# SCH_birdo_2021-11-24.net
KiCad netlist of a schematic drawn in EasyEDA
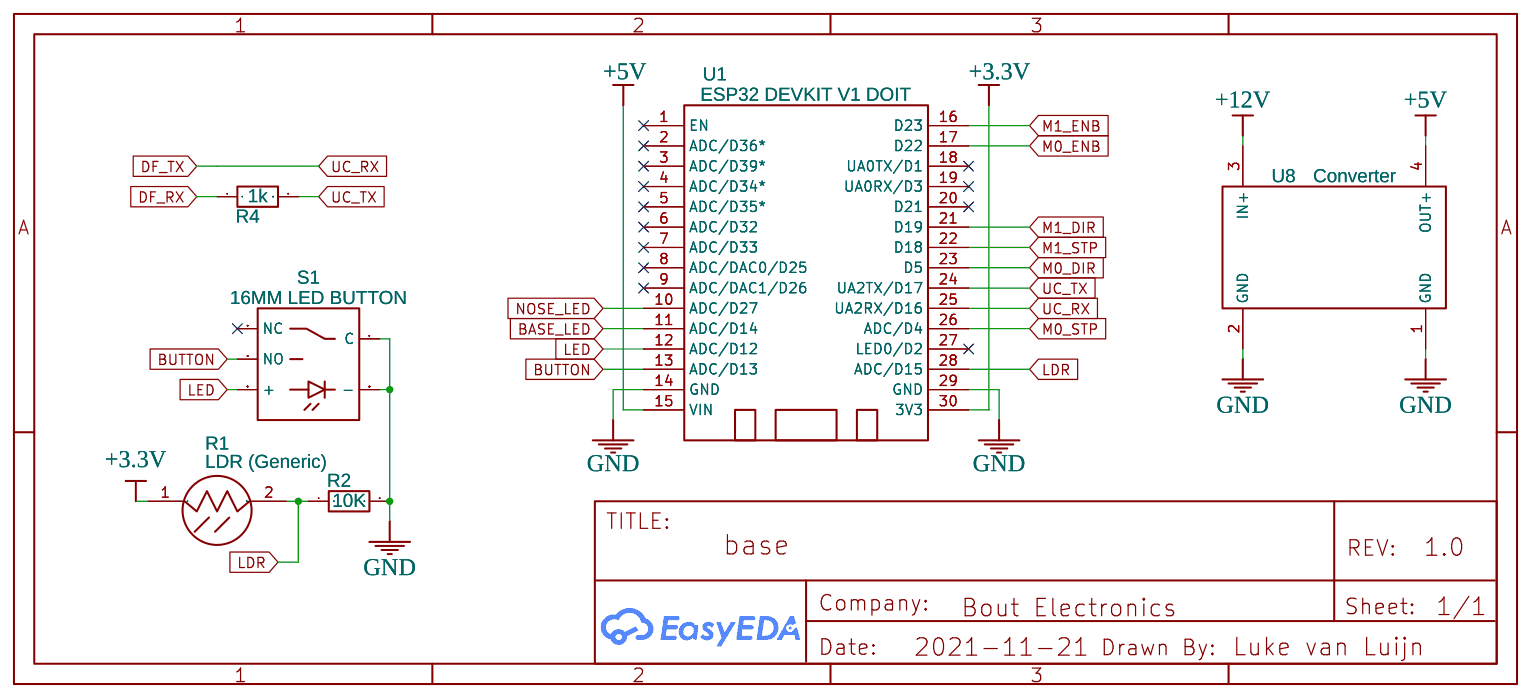
[diagram p0: base]
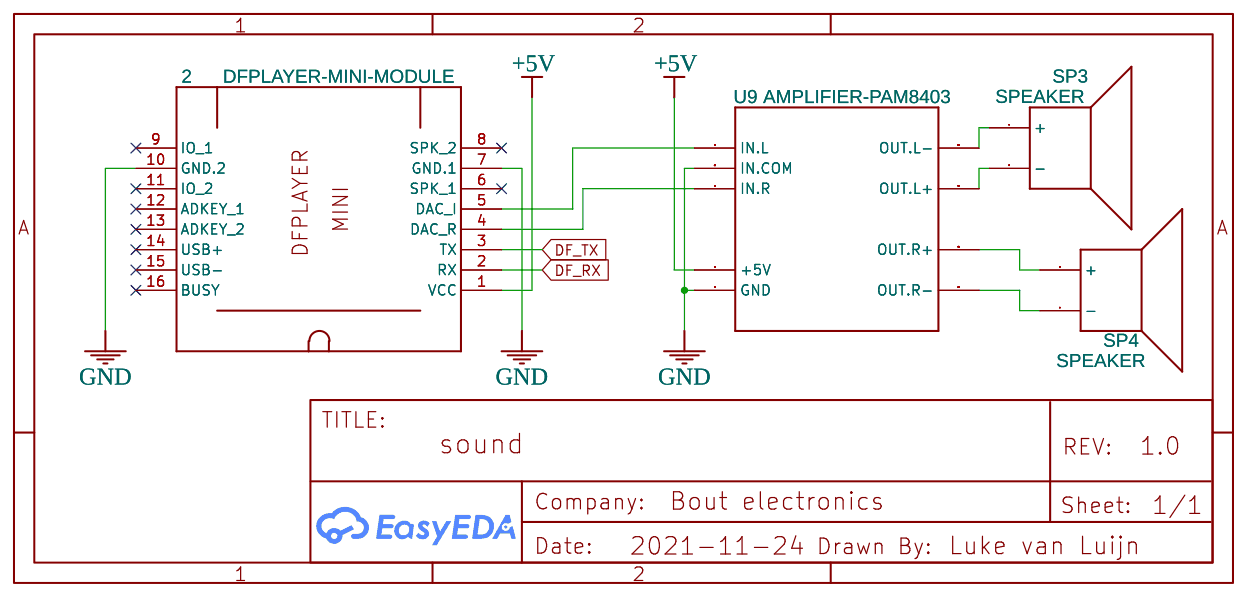
[diagram p1: sound]
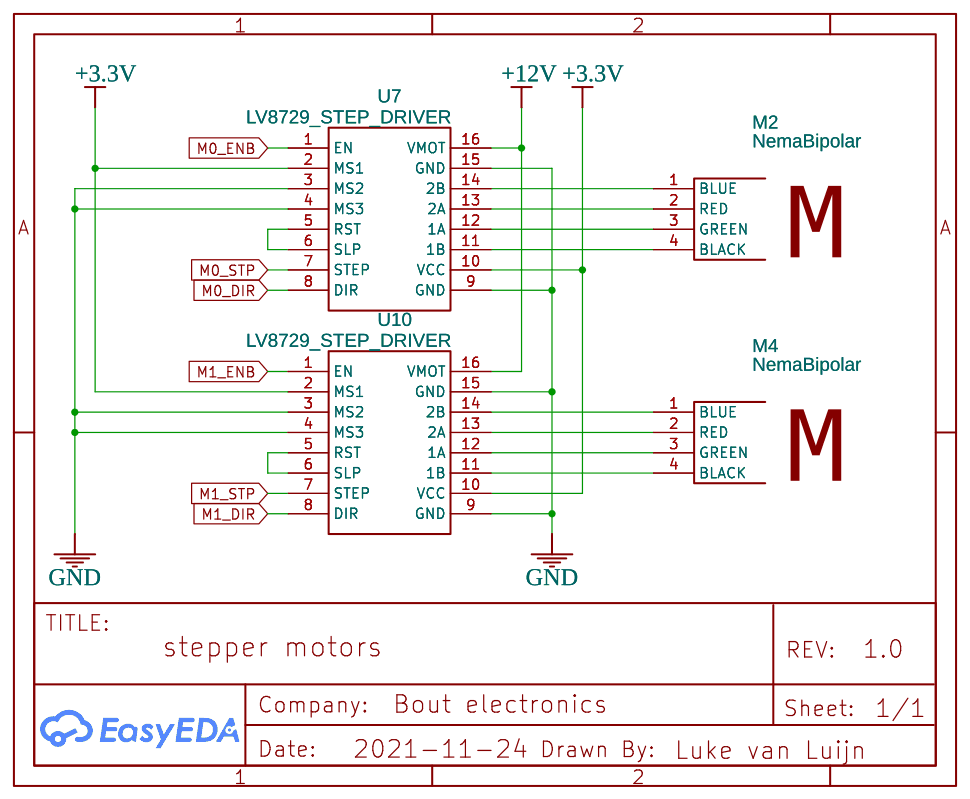
[diagram p2: motors]
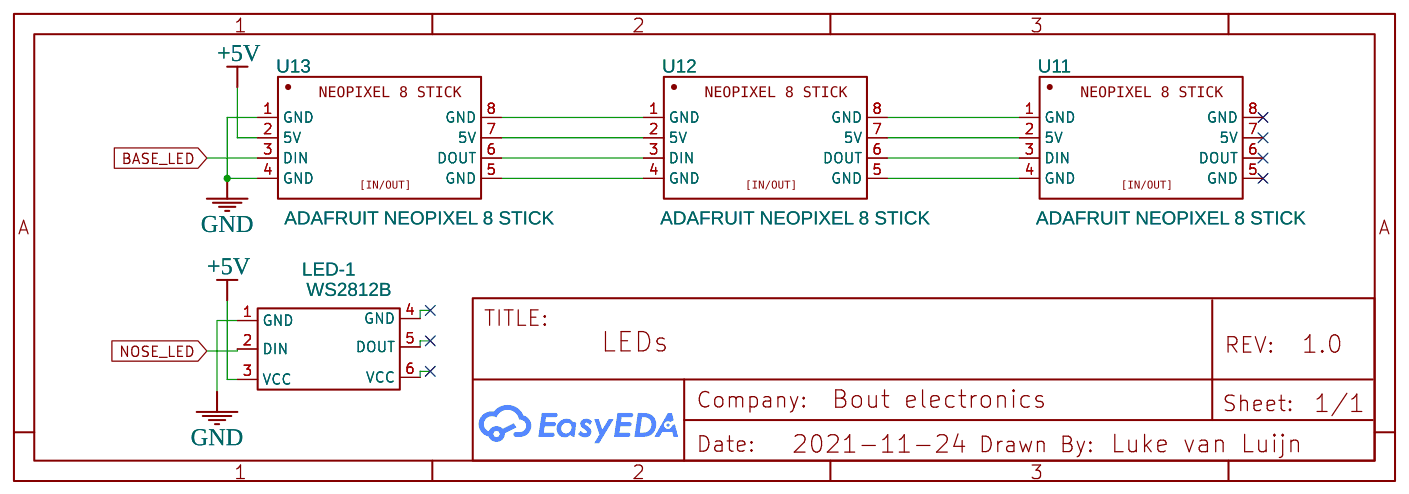
[diagram p3: LEDs]

(export (version "E")
  (design (tool "Eeschema 10.0.6"))
  (components
    (comp (ref "R1") (value "LDR (Generic)") (libsource (lib "") (part "LDR (Generic)")))
    (comp (ref "R2") (value "10K") (libsource (lib "") (part "R_AXIAL-0.3_EU")))
    (comp (ref "R4") (value "1k") (libsource (lib "") (part "R_AXIAL-0.3_EU")))
    (comp (ref "S1")
      (value "16MM LED BUTTON")
      (fields
        (field (name "BOM_Manufacturer Part") "LED BTN")
        (field (name "BOM_Supplier Part") "16mm Momentary Push Button 12V")
      )
      (libsource (lib "") (part "16MM LED 12V MOMENTARY PUSH BUTTON"))
    )
    (comp (ref "U1") (value "ESP32 DEVKIT V1 DOIT") (libsource (lib "") (part "ESP32 DEVKIT V1 DOIT")))
    (comp (ref "U8") (value "Converter") (libsource (lib "") (part "StepDownConverter")))
    (comp (ref "2") (value "DFPLAYER-MINI-MODULE") (libsource (lib "") (part "DFPLAYER-MINI-MODULE")))
    (comp (ref "SP3") (value "SPEAKER") (libsource (lib "") (part "SPEAKER")))
    (comp (ref "SP4") (value "SPEAKER") (libsource (lib "") (part "SPEAKER")))
    (comp (ref "U9") (value "AMPLIFIER-PAM8403") (libsource (lib "") (part "AMPLIFIER-PAM8403")))
    (comp (ref "M2") (value "NemaBipolar") (libsource (lib "") (part "NemaBipolar")))
    (comp (ref "M4") (value "NemaBipolar") (libsource (lib "") (part "NemaBipolar")))
    (comp (ref "U7")
      (value "LV8729_STEP_DRIVER")
      (fields (field (name "BOM_Manufacturer Part") "A4988 MODULE"))
      (libsource (lib "") (part "LV8729_STEP_DRIVER"))
    )
    (comp (ref "U10")
      (value "LV8729_STEP_DRIVER")
      (fields (field (name "BOM_Manufacturer Part") "A4988 MODULE"))
      (libsource (lib "") (part "LV8729_STEP_DRIVER"))
    )
    (comp (ref "LED-1") (value "WS2812B") (libsource (lib "") (part "WS2812B")))
    (comp (ref "U11")
      (value "ADAFRUIT NEOPIXEL 8 STICK")
      (fields (field (name "BOM_Manufacturer Part") "1426") (field (name "BOM_Supplier Part") "1528-1354-ND"))
      (libsource (lib "") (part "ADAFRUIT NEOPIXEL 8 STICK [IN/OUT]"))
    )
    (comp (ref "U12")
      (value "ADAFRUIT NEOPIXEL 8 STICK")
      (fields (field (name "BOM_Manufacturer Part") "1426") (field (name "BOM_Supplier Part") "1528-1354-ND"))
      (libsource (lib "") (part "ADAFRUIT NEOPIXEL 8 STICK [IN/OUT]"))
    )
    (comp (ref "U13")
      (value "ADAFRUIT NEOPIXEL 8 STICK")
      (fields (field (name "BOM_Manufacturer Part") "1426") (field (name "BOM_Supplier Part") "1528-1354-ND"))
      (libsource (lib "") (part "ADAFRUIT NEOPIXEL 8 STICK [IN/OUT]"))
    )
  )
  (nets
    (net (code "1") (name "+3.3V") (class "Default")
      (node (ref "R1") (pin "1") (pinfunction "1_1") (pintype "unspecified"))
      (node (ref "U1") (pin "30") (pinfunction "3V3_30") (pintype "bidirectional"))
      (node (ref "U10") (pin "10") (pinfunction "VCC_10") (pintype "unspecified"))
      (node (ref "U10") (pin "2") (pinfunction "MS1_2") (pintype "unspecified"))
      (node (ref "U7") (pin "10") (pinfunction "VCC_10") (pintype "unspecified"))
      (node (ref "U7") (pin "2") (pinfunction "MS1_2") (pintype "unspecified"))
    )
    (net (code "2") (name "+5V") (class "Default")
      (node (ref "2") (pin "1") (pinfunction "VCC_1") (pintype "bidirectional"))
      (node (ref "LED-1") (pin "3") (pinfunction "VCC_3") (pintype "unspecified"))
      (node (ref "U1") (pin "15") (pinfunction "VIN_15") (pintype "input"))
      (node (ref "U13") (pin "2") (pinfunction "5V_2") (pintype "unspecified"))
      (node (ref "U8") (pin "4") (pinfunction "OUT+_4") (pintype "unspecified"))
      (node (ref "U9") (pin "+5V") (pinfunction "+5V_+5V") (pintype "passive"))
    )
    (net (code "3") (name "+12V") (class "Default")
      (node (ref "U10") (pin "16") (pinfunction "VMOT_16") (pintype "unspecified"))
      (node (ref "U7") (pin "16") (pinfunction "VMOT_16") (pintype "unspecified"))
      (node (ref "U8") (pin "3") (pinfunction "IN+_3") (pintype "unspecified"))
    )
    (net (code "4") (name "BASE_LED") (class "Default")
      (node (ref "U1") (pin "11") (pinfunction "ADC/D14_11") (pintype "bidirectional"))
      (node (ref "U13") (pin "3") (pinfunction "DIN_3") (pintype "unspecified"))
    )
    (net (code "5") (name "BUTTON") (class "Default")
      (node (ref "S1") (pin "NO") (pinfunction "NO_NO") (pintype "unspecified"))
      (node (ref "U1") (pin "13") (pinfunction "ADC/D13_13") (pintype "bidirectional"))
    )
    (net (code "6") (name "DF_RX") (class "Default")
      (node (ref "2") (pin "2") (pinfunction "RX_2") (pintype "bidirectional"))
      (node (ref "R4") (pin "1") (pinfunction "1_1") (pintype "unspecified"))
    )
    (net (code "7") (name "DF_TX") (class "Default")
      (node (ref "2") (pin "3") (pinfunction "TX_3") (pintype "bidirectional"))
      (node (ref "U1") (pin "25") (pinfunction "UA2RX/D16_25") (pintype "bidirectional"))
    )
    (net (code "8") (name "GND") (class "Default")
      (node (ref "2") (pin "10") (pinfunction "GND.2_10") (pintype "bidirectional"))
      (node (ref "2") (pin "7") (pinfunction "GND.1_7") (pintype "bidirectional"))
      (node (ref "LED-1") (pin "1") (pinfunction "GND_1") (pintype "unspecified"))
      (node (ref "R2") (pin "2") (pinfunction "2_2") (pintype "unspecified"))
      (node (ref "S1") (pin "C") (pinfunction "C_C") (pintype "unspecified"))
      (node (ref "S1") (pin "GND") (pinfunction "-_GND") (pintype "unspecified"))
      (node (ref "U1") (pin "14") (pinfunction "GND_14") (pintype "bidirectional"))
      (node (ref "U1") (pin "29") (pinfunction "GND_29") (pintype "bidirectional"))
      (node (ref "U10") (pin "15") (pinfunction "GND_15") (pintype "unspecified"))
      (node (ref "U10") (pin "3") (pinfunction "MS2_3") (pintype "unspecified"))
      (node (ref "U10") (pin "4") (pinfunction "MS3_4") (pintype "unspecified"))
      (node (ref "U10") (pin "9") (pinfunction "GND_9") (pintype "unspecified"))
      (node (ref "U13") (pin "1") (pinfunction "GND_1") (pintype "unspecified"))
      (node (ref "U13") (pin "4") (pinfunction "GND_4") (pintype "unspecified"))
      (node (ref "U7") (pin "15") (pinfunction "GND_15") (pintype "unspecified"))
      (node (ref "U7") (pin "3") (pinfunction "MS2_3") (pintype "unspecified"))
      (node (ref "U7") (pin "4") (pinfunction "MS3_4") (pintype "unspecified"))
      (node (ref "U7") (pin "9") (pinfunction "GND_9") (pintype "unspecified"))
      (node (ref "U8") (pin "1") (pinfunction "GND_1") (pintype "unspecified"))
      (node (ref "U8") (pin "2") (pinfunction "GND_2") (pintype "unspecified"))
      (node (ref "U9") (pin "GND") (pinfunction "GND_GND") (pintype "passive"))
      (node (ref "U9") (pin "IN.COM") (pinfunction "IN.COM_IN.COM") (pintype "input"))
    )
    (net (code "9") (name "LDR") (class "Default")
      (node (ref "R1") (pin "2") (pinfunction "2_2") (pintype "unspecified"))
      (node (ref "R2") (pin "1") (pinfunction "1_1") (pintype "unspecified"))
      (node (ref "U1") (pin "28") (pinfunction "ADC/D15_28") (pintype "bidirectional"))
    )
    (net (code "10") (name "LED") (class "Default")
      (node (ref "S1") (pin "VCC") (pinfunction "+_VCC") (pintype "unspecified"))
      (node (ref "U1") (pin "12") (pinfunction "ADC/D12_12") (pintype "bidirectional"))
    )
    (net (code "11") (name "M0_DIR") (class "Default")
      (node (ref "U1") (pin "23") (pinfunction "D5_23") (pintype "bidirectional"))
      (node (ref "U7") (pin "8") (pinfunction "DIR_8") (pintype "unspecified"))
    )
    (net (code "12") (name "M0_ENB") (class "Default")
      (node (ref "U1") (pin "17") (pinfunction "D22_17") (pintype "bidirectional"))
      (node (ref "U7") (pin "1") (pinfunction "EN_1") (pintype "unspecified"))
    )
    (net (code "13") (name "M0_STP") (class "Default")
      (node (ref "U1") (pin "26") (pinfunction "ADC/D4_26") (pintype "bidirectional"))
      (node (ref "U7") (pin "7") (pinfunction "STEP_7") (pintype "unspecified"))
    )
    (net (code "14") (name "M1_DIR") (class "Default")
      (node (ref "U1") (pin "21") (pinfunction "D19_21") (pintype "bidirectional"))
      (node (ref "U10") (pin "8") (pinfunction "DIR_8") (pintype "unspecified"))
    )
    (net (code "15") (name "M1_ENB") (class "Default")
      (node (ref "U1") (pin "16") (pinfunction "D23_16") (pintype "bidirectional"))
      (node (ref "U10") (pin "1") (pinfunction "EN_1") (pintype "unspecified"))
    )
    (net (code "16") (name "M1_STP") (class "Default")
      (node (ref "U1") (pin "22") (pinfunction "D18_22") (pintype "bidirectional"))
      (node (ref "U10") (pin "7") (pinfunction "STEP_7") (pintype "unspecified"))
    )
    (net (code "17") (name "NOSE_LED") (class "Default")
      (node (ref "LED-1") (pin "2") (pinfunction "DIN_2") (pintype "unspecified"))
      (node (ref "U1") (pin "10") (pinfunction "ADC/D27_10") (pintype "bidirectional"))
    )
    (net (code "18") (name "Net-(2-DAC_I)") (class "Default")
      (node (ref "2") (pin "5") (pinfunction "DAC_I_5") (pintype "bidirectional"))
      (node (ref "U9") (pin "IN.L") (pinfunction "IN.L_IN.L") (pintype "input"))
    )
    (net (code "19") (name "Net-(2-DAC_R)") (class "Default")
      (node (ref "2") (pin "4") (pinfunction "DAC_R_4") (pintype "bidirectional"))
      (node (ref "U9") (pin "IN.R") (pinfunction "IN.R_IN.R") (pintype "unspecified"))
    )
    (net (code "20") (name "Net-(M2-BLACK)") (class "Default")
      (node (ref "M2") (pin "4") (pinfunction "BLACK_4") (pintype "input"))
      (node (ref "U7") (pin "11") (pinfunction "1B_11") (pintype "unspecified"))
    )
    (net (code "21") (name "Net-(M2-BLUE)") (class "Default")
      (node (ref "M2") (pin "1") (pinfunction "BLUE_1") (pintype "input"))
      (node (ref "U7") (pin "14") (pinfunction "2B_14") (pintype "unspecified"))
    )
    (net (code "22") (name "Net-(M2-GREEN)") (class "Default")
      (node (ref "M2") (pin "3") (pinfunction "GREEN_3") (pintype "input"))
      (node (ref "U7") (pin "12") (pinfunction "1A_12") (pintype "unspecified"))
    )
    (net (code "23") (name "Net-(M2-RED)") (class "Default")
      (node (ref "M2") (pin "2") (pinfunction "RED_2") (pintype "input"))
      (node (ref "U7") (pin "13") (pinfunction "2A_13") (pintype "unspecified"))
    )
    (net (code "24") (name "Net-(M4-BLACK)") (class "Default")
      (node (ref "M4") (pin "4") (pinfunction "BLACK_4") (pintype "input"))
      (node (ref "U10") (pin "11") (pinfunction "1B_11") (pintype "unspecified"))
    )
    (net (code "25") (name "Net-(M4-BLUE)") (class "Default")
      (node (ref "M4") (pin "1") (pinfunction "BLUE_1") (pintype "input"))
      (node (ref "U10") (pin "14") (pinfunction "2B_14") (pintype "unspecified"))
    )
    (net (code "26") (name "Net-(M4-GREEN)") (class "Default")
      (node (ref "M4") (pin "3") (pinfunction "GREEN_3") (pintype "input"))
      (node (ref "U10") (pin "12") (pinfunction "1A_12") (pintype "unspecified"))
    )
    (net (code "27") (name "Net-(M4-RED)") (class "Default")
      (node (ref "M4") (pin "2") (pinfunction "RED_2") (pintype "input"))
      (node (ref "U10") (pin "13") (pinfunction "2A_13") (pintype "unspecified"))
    )
    (net (code "28") (name "Net-(SP3-+)") (class "Default")
      (node (ref "SP3") (pin "1") (pinfunction "+_1") (pintype "bidirectional"))
      (node (ref "U9") (pin "OUT.L-") (pinfunction "OUT.L-_OUT.L-") (pintype "output"))
    )
    (net (code "29") (name "Net-(SP3--)") (class "Default")
      (node (ref "SP3") (pin "2") (pinfunction "-_2") (pintype "bidirectional"))
      (node (ref "U9") (pin "OUT.L+") (pinfunction "OUT.L+_OUT.L+") (pintype "output"))
    )
    (net (code "30") (name "Net-(SP4-+)") (class "Default")
      (node (ref "SP4") (pin "1") (pinfunction "+_1") (pintype "bidirectional"))
      (node (ref "U9") (pin "OUT.R+") (pinfunction "OUT.R+_OUT.R+") (pintype "output"))
    )
    (net (code "31") (name "Net-(SP4--)") (class "Default")
      (node (ref "SP4") (pin "2") (pinfunction "-_2") (pintype "bidirectional"))
      (node (ref "U9") (pin "OUT.R-") (pinfunction "OUT.R-_OUT.R-") (pintype "output"))
    )
    (net (code "32") (name "Net-(U7-RST)") (class "Default")
      (node (ref "U7") (pin "5") (pinfunction "RST_5") (pintype "unspecified"))
      (node (ref "U7") (pin "6") (pinfunction "SLP_6") (pintype "unspecified"))
    )
    (net (code "33") (name "Net-(U10-RST)") (class "Default")
      (node (ref "U10") (pin "5") (pinfunction "RST_5") (pintype "unspecified"))
      (node (ref "U10") (pin "6") (pinfunction "SLP_6") (pintype "unspecified"))
    )
    (net (code "34") (name "Net-(U11-5V-Pad2)") (class "Default")
      (node (ref "U11") (pin "2") (pinfunction "5V_2") (pintype "unspecified"))
      (node (ref "U12") (pin "7") (pinfunction "5V_7") (pintype "unspecified"))
    )
    (net (code "35") (name "Net-(U11-DIN)") (class "Default")
      (node (ref "U11") (pin "3") (pinfunction "DIN_3") (pintype "unspecified"))
      (node (ref "U12") (pin "6") (pinfunction "DOUT_6") (pintype "unspecified"))
    )
    (net (code "36") (name "Net-(U11-GND-Pad1)") (class "Default")
      (node (ref "U11") (pin "1") (pinfunction "GND_1") (pintype "unspecified"))
      (node (ref "U12") (pin "8") (pinfunction "GND_8") (pintype "unspecified"))
    )
    (net (code "37") (name "Net-(U11-GND-Pad4)") (class "Default")
      (node (ref "U11") (pin "4") (pinfunction "GND_4") (pintype "unspecified"))
      (node (ref "U12") (pin "5") (pinfunction "GND_5") (pintype "unspecified"))
    )
    (net (code "38") (name "Net-(U12-5V-Pad2)") (class "Default")
      (node (ref "U12") (pin "2") (pinfunction "5V_2") (pintype "unspecified"))
      (node (ref "U13") (pin "7") (pinfunction "5V_7") (pintype "unspecified"))
    )
    (net (code "39") (name "Net-(U12-DIN)") (class "Default")
      (node (ref "U12") (pin "3") (pinfunction "DIN_3") (pintype "unspecified"))
      (node (ref "U13") (pin "6") (pinfunction "DOUT_6") (pintype "unspecified"))
    )
    (net (code "40") (name "Net-(U12-GND-Pad1)") (class "Default")
      (node (ref "U12") (pin "1") (pinfunction "GND_1") (pintype "unspecified"))
      (node (ref "U13") (pin "8") (pinfunction "GND_8") (pintype "unspecified"))
    )
    (net (code "41") (name "Net-(U12-GND-Pad4)") (class "Default")
      (node (ref "U12") (pin "4") (pinfunction "GND_4") (pintype "unspecified"))
      (node (ref "U13") (pin "5") (pinfunction "GND_5") (pintype "unspecified"))
    )
    (net (code "42") (name "UC_TX") (class "Default")
      (node (ref "R4") (pin "2") (pinfunction "2_2") (pintype "unspecified"))
      (node (ref "U1") (pin "24") (pinfunction "UA2TX/D17_24") (pintype "bidirectional"))
    )
    (net (code "43") (name "unconnected-(2-ADKEY_1-Pad12)") (class "Default")
      (node (ref "2") (pin "12") (pinfunction "ADKEY_1_12") (pintype "bidirectional+no_connect"))
    )
    (net (code "44") (name "unconnected-(2-ADKEY_2-Pad13)") (class "Default")
      (node (ref "2") (pin "13") (pinfunction "ADKEY_2_13") (pintype "bidirectional+no_connect"))
    )
    (net (code "45") (name "unconnected-(2-BUSY-Pad16)") (class "Default")
      (node (ref "2") (pin "16") (pinfunction "BUSY_16") (pintype "bidirectional+no_connect"))
    )
    (net (code "46") (name "unconnected-(2-IO_1-Pad9)") (class "Default")
      (node (ref "2") (pin "9") (pinfunction "IO_1_9") (pintype "bidirectional+no_connect"))
    )
    (net (code "47") (name "unconnected-(2-IO_2-Pad11)") (class "Default")
      (node (ref "2") (pin "11") (pinfunction "IO_2_11") (pintype "bidirectional+no_connect"))
    )
    (net (code "48") (name "unconnected-(2-SPK_1-Pad6)") (class "Default")
      (node (ref "2") (pin "6") (pinfunction "SPK_1_6") (pintype "bidirectional+no_connect"))
    )
    (net (code "49") (name "unconnected-(2-SPK_2-Pad8)") (class "Default")
      (node (ref "2") (pin "8") (pinfunction "SPK_2_8") (pintype "bidirectional+no_connect"))
    )
    (net (code "50") (name "unconnected-(2-USB+-Pad14)") (class "Default")
      (node (ref "2") (pin "14") (pinfunction "USB+_14") (pintype "bidirectional+no_connect"))
    )
    (net (code "51") (name "unconnected-(2-USB--Pad15)") (class "Default")
      (node (ref "2") (pin "15") (pinfunction "USB-_15") (pintype "bidirectional+no_connect"))
    )
    (net (code "52") (name "unconnected-(LED-1-DOUT-Pad5)") (class "Default")
      (node (ref "LED-1") (pin "5") (pinfunction "DOUT_5") (pintype "unspecified+no_connect"))
    )
    (net (code "53") (name "unconnected-(LED-1-GND-Pad4)") (class "Default")
      (node (ref "LED-1") (pin "4") (pinfunction "GND_4") (pintype "unspecified+no_connect"))
    )
    (net (code "54") (name "unconnected-(LED-1-VCC-Pad6)") (class "Default")
      (node (ref "LED-1") (pin "6") (pinfunction "VCC_6") (pintype "unspecified+no_connect"))
    )
    (net (code "55") (name "unconnected-(S1-PadNC)") (class "Default")
      (node (ref "S1") (pin "NC") (pinfunction "NC_NC") (pintype "unspecified+no_connect"))
    )
    (net (code "56") (name "unconnected-(U1-ADC{slash}D32-Pad6)") (class "Default")
      (node (ref "U1") (pin "6") (pinfunction "ADC/D32_6") (pintype "bidirectional+no_connect"))
    )
    (net (code "57") (name "unconnected-(U1-ADC{slash}D33-Pad7)") (class "Default")
      (node (ref "U1") (pin "7") (pinfunction "ADC/D33_7") (pintype "bidirectional+no_connect"))
    )
    (net (code "58") (name "unconnected-(U1-ADC{slash}D34*-Pad4)") (class "Default")
      (node (ref "U1") (pin "4") (pinfunction "ADC/D34*_4") (pintype "input+no_connect"))
    )
    (net (code "59") (name "unconnected-(U1-ADC{slash}D35*-Pad5)") (class "Default")
      (node (ref "U1") (pin "5") (pinfunction "ADC/D35*_5") (pintype "input+no_connect"))
    )
    (net (code "60") (name "unconnected-(U1-ADC{slash}D36*-Pad2)") (class "Default")
      (node (ref "U1") (pin "2") (pinfunction "ADC/D36*_2") (pintype "input+no_connect"))
    )
    (net (code "61") (name "unconnected-(U1-ADC{slash}D39*-Pad3)") (class "Default")
      (node (ref "U1") (pin "3") (pinfunction "ADC/D39*_3") (pintype "input+no_connect"))
    )
    (net (code "62") (name "unconnected-(U1-ADC{slash}DAC0{slash}D25-Pad8)") (class "Default")
      (node (ref "U1") (pin "8") (pinfunction "ADC/DAC0/D25_8") (pintype "bidirectional+no_connect"))
    )
    (net (code "63") (name "unconnected-(U1-ADC{slash}DAC1{slash}D26-Pad9)") (class "Default")
      (node (ref "U1") (pin "9") (pinfunction "ADC/DAC1/D26_9") (pintype "bidirectional+no_connect"))
    )
    (net (code "64") (name "unconnected-(U1-D21-Pad20)") (class "Default")
      (node (ref "U1") (pin "20") (pinfunction "D21_20") (pintype "bidirectional+no_connect"))
    )
    (net (code "65") (name "unconnected-(U1-EN-Pad1)") (class "Default")
      (node (ref "U1") (pin "1") (pinfunction "EN_1") (pintype "bidirectional+no_connect"))
    )
    (net (code "66") (name "unconnected-(U1-LED0{slash}D2-Pad27)") (class "Default")
      (node (ref "U1") (pin "27") (pinfunction "LED0/D2_27") (pintype "bidirectional+no_connect"))
    )
    (net (code "67") (name "unconnected-(U1-UA0RX{slash}D3-Pad19)") (class "Default")
      (node (ref "U1") (pin "19") (pinfunction "UA0RX/D3_19") (pintype "bidirectional+no_connect"))
    )
    (net (code "68") (name "unconnected-(U1-UA0TX{slash}D1-Pad18)") (class "Default")
      (node (ref "U1") (pin "18") (pinfunction "UA0TX/D1_18") (pintype "bidirectional+no_connect"))
    )
    (net (code "69") (name "unconnected-(U11-5V-Pad7)") (class "Default")
      (node (ref "U11") (pin "7") (pinfunction "5V_7") (pintype "unspecified+no_connect"))
    )
    (net (code "70") (name "unconnected-(U11-DOUT-Pad6)") (class "Default")
      (node (ref "U11") (pin "6") (pinfunction "DOUT_6") (pintype "unspecified+no_connect"))
    )
    (net (code "71") (name "unconnected-(U11-GND-Pad5)") (class "Default")
      (node (ref "U11") (pin "5") (pinfunction "GND_5") (pintype "unspecified+no_connect"))
    )
    (net (code "72") (name "unconnected-(U11-GND-Pad8)") (class "Default")
      (node (ref "U11") (pin "8") (pinfunction "GND_8") (pintype "unspecified+no_connect"))
    )
  )
)
